# Main.net
KiCad netlist of a schematic drawn in Altium Designer
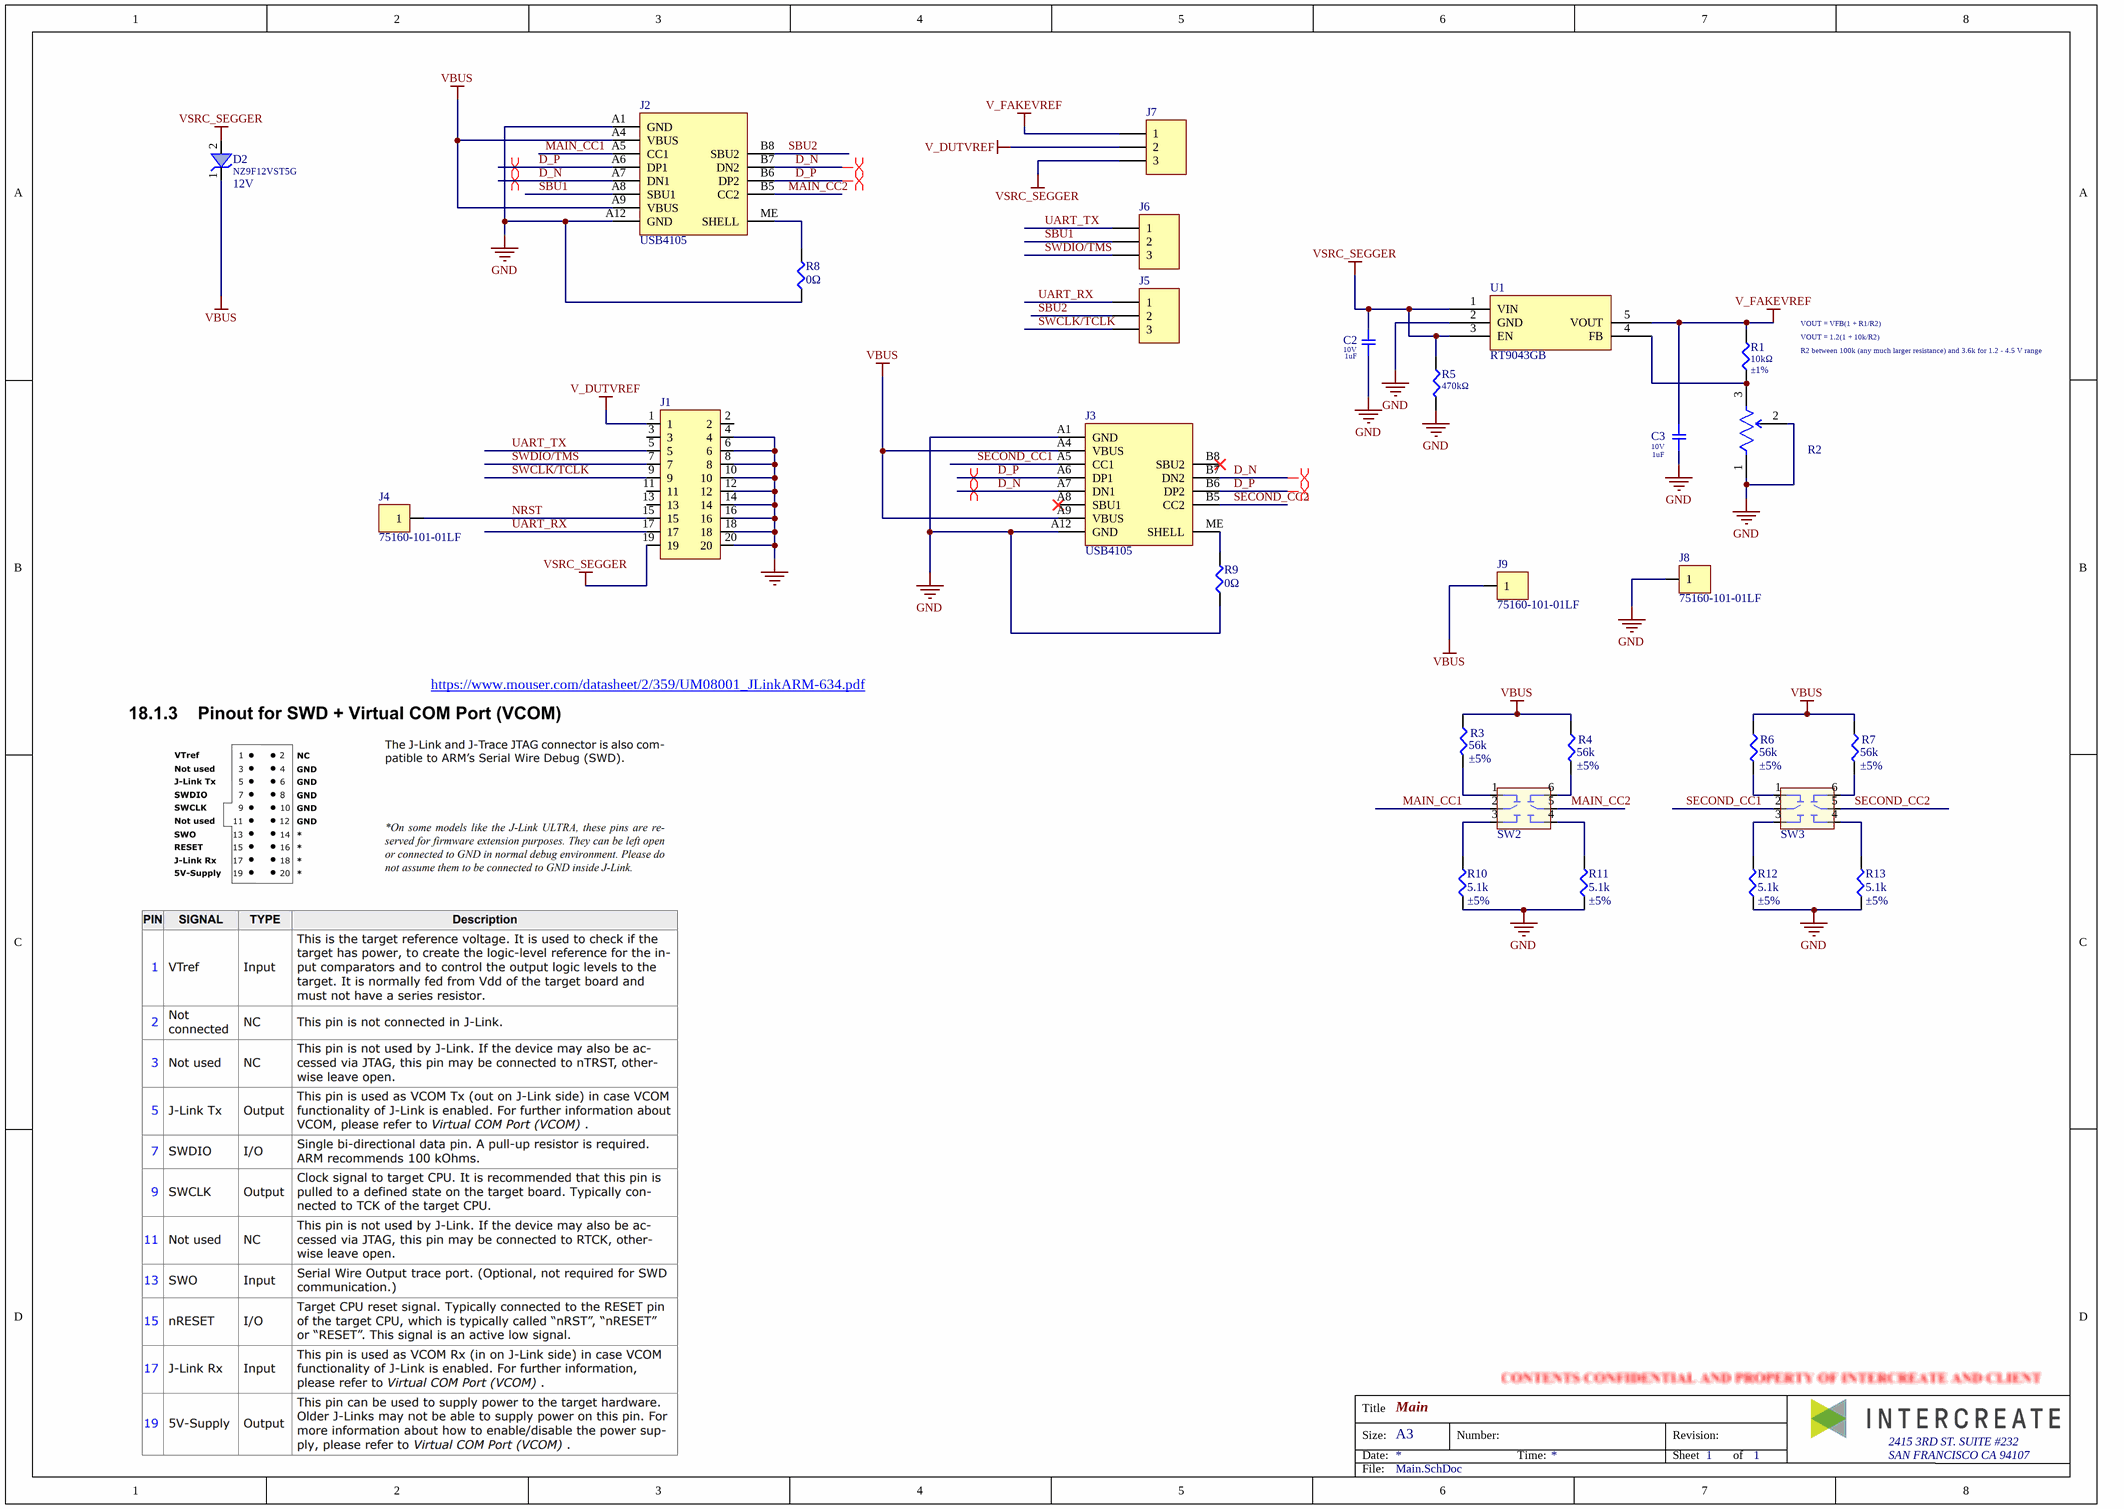
[diagram p0: Main.SchDoc]

(export (version "E")
  (design (tool "Eeschema 10.0.6"))
  (components
    (comp (ref "C2")
      (value "0402ZD105KAT2A")
      (footprint "CAP-0402")
      (fields
        (field (name "TOLERANCE") "10%")
        (field (name "VOLTAGE") "10V")
        (field (name "VOLTAGE RATING") "10V")
        (field (name "CAPACITANCE") "1uF")
      )
      (libsource (lib "intercreate") (part "CAP-1uF-10V-0402"))
    )
    (comp (ref "C3")
      (value "0402ZD105KAT2A")
      (footprint "CAP-0402")
      (fields
        (field (name "TOLERANCE") "10%")
        (field (name "VOLTAGE") "10V")
        (field (name "VOLTAGE RATING") "10V")
        (field (name "CAPACITANCE") "1uF")
      )
      (libsource (lib "intercreate") (part "CAP-1uF-10V-0402"))
    )
    (comp (ref "D2")
      (value "NZ9F12VST5G")
      (footprint "DIODE-SOD923")
      (description "DIODE ZENER 12V 200MW SOD923")
      (fields (field (name "TOLERANCE") "2%") (field (name "ZENER VOLTAGE") "12V"))
      (libsource (lib "intercreate") (part "DIODE-ZNR-12V-SOD923"))
    )
    (comp (ref "J1")
      (value "SFH11-PBPC-D10-ST-BK")
      (footprint "HDR-V-2X10-F-2.54MM")
      (description "20 Position Header Connector 0.100\" (2.54mm) Through Hole Gold")
      (libsource (lib "intercreate") (part "HDR-V-2X10-F-2.54MM"))
    )
    (comp (ref "J2")
      (value "USB4105")
      (footprint "CONN-USBC-GCT_USB4105")
      (description "Usb Conn, 2.0 Type C, Rcpt, 16Pos, Smt Rohs Compliant: Yes")
      (libsource (lib "intercreate") (part "CONN-F-USB-C-GCT_USB4105"))
    )
    (comp (ref "J3")
      (value "USB4105")
      (footprint "CONN-USBC-GCT_USB4105")
      (description "Usb Conn, 2.0 Type C, Rcpt, 16Pos, Smt Rohs Compliant: Yes")
      (libsource (lib "intercreate") (part "CONN-F-USB-C-GCT_USB4105"))
    )
    (comp (ref "J4")
      (value "75160-101-01LF")
      (footprint "HDR-V-1X1-M")
      (libsource (lib "") (part "HDR-V-1X1-M_1"))
    )
    (comp (ref "J5")
      (value "61300311121")
      (footprint "HDR-V-1X3")
      (description "Header, 3-Pin, 0.1\"")
      (fields (field (name "MANUFACTURER") "Wurth Electronics") (field (name "PUBLISHER") "Altium Limited"))
      (libsource (lib "intercreate") (part "HDR-V-1X3-M"))
    )
    (comp (ref "J6")
      (value "61300311121")
      (footprint "HDR-V-1X3")
      (description "Header, 3-Pin, 0.1\"")
      (fields (field (name "MANUFACTURER") "Wurth Electronics") (field (name "PUBLISHER") "Altium Limited"))
      (libsource (lib "intercreate") (part "HDR-V-1X3-M"))
    )
    (comp (ref "J7")
      (value "61300311121")
      (footprint "HDR-V-1X3")
      (description "Header, 3-Pin, 0.1\"")
      (fields (field (name "MANUFACTURER") "Wurth Electronics") (field (name "PUBLISHER") "Altium Limited"))
      (libsource (lib "intercreate") (part "HDR-V-1X3-M"))
    )
    (comp (ref "J8")
      (value "75160-101-01LF")
      (footprint "HDR-V-1X1-M")
      (libsource (lib "intercreate") (part "HDR-V-1X1-M"))
    )
    (comp (ref "J9")
      (value "75160-101-01LF")
      (footprint "HDR-V-1X1-M")
      (libsource (lib "intercreate") (part "HDR-V-1X1-M"))
    )
    (comp (ref "R1")
      (value "10kΩ")
      (footprint "RES-0402")
      (description "RES SMD 10K OHM 1% 1/16W 0402")
      (fields (field (name "TOLERANCE") "±1%") (field (name "Comment") "RC0402FR-0710KL"))
      (libsource (lib "intercreate") (part "RES-10K-0402"))
    )
    (comp (ref "R2")
      (value "POT-ROT-100K-SMD")
      (footprint "3361P-1-104GLF")
      (description "TRIMMER 100K OHM 0.5W GW TOP ADJ")
      (libsource (lib "intercreate") (part "POT-ROT-100K-SMD"))
    )
    (comp (ref "R3")
      (value "56k")
      (footprint "RES-0402")
      (description "RES SMD 56K OHM 5% 1/10W 0402")
      (fields
        (field (name "MANUFACTURER") "Panasonic")
        (field (name "MANUFACTURER PART NUMBER") "ERJ2GEJ563X")
        (field (name "TOLERANCE") "±5%")
      )
      (libsource (lib "intercreate") (part "RES-56K-0402-5%"))
    )
    (comp (ref "R4")
      (value "56k")
      (footprint "RES-0402")
      (description "RES SMD 56K OHM 5% 1/10W 0402")
      (fields
        (field (name "MANUFACTURER") "Panasonic")
        (field (name "MANUFACTURER PART NUMBER") "ERJ2GEJ563X")
        (field (name "TOLERANCE") "±5%")
      )
      (libsource (lib "intercreate") (part "RES-56K-0402-5%"))
    )
    (comp (ref "R5")
      (value "470kΩ")
      (footprint "RES-0402")
      (description "RES SMD 470K OHM 1% 1/16W 0402")
      (fields (field (name "TOLERANCE") "1%") (field (name "Comment") "RES-470K-0402"))
      (libsource (lib "Intercreate") (part "RES-95.3K-0402-0.1"))
    )
    (comp (ref "R6")
      (value "56k")
      (footprint "RES-0402")
      (description "RES SMD 56K OHM 5% 1/10W 0402")
      (fields
        (field (name "MANUFACTURER") "Panasonic")
        (field (name "MANUFACTURER PART NUMBER") "ERJ2GEJ563X")
        (field (name "TOLERANCE") "±5%")
      )
      (libsource (lib "intercreate") (part "RES-56K-0402-5%"))
    )
    (comp (ref "R7")
      (value "56k")
      (footprint "RES-0402")
      (description "RES SMD 56K OHM 5% 1/10W 0402")
      (fields
        (field (name "MANUFACTURER") "Panasonic")
        (field (name "MANUFACTURER PART NUMBER") "ERJ2GEJ563X")
        (field (name "TOLERANCE") "±5%")
      )
      (libsource (lib "intercreate") (part "RES-56K-0402-5%"))
    )
    (comp (ref "R8")
      (value "0Ω")
      (footprint "RES-0402")
      (description "RES 0 OHM JUMPER 1/16W 0402")
      (fields
        (field (name "MANUFACTURER") "Yageo")
        (field (name "MANUFACTURER PART NUMBER") "RC0402FR-070RL")
      )
      (libsource (lib "intercreate") (part "RES-0-0402"))
    )
    (comp (ref "R9")
      (value "0Ω")
      (footprint "RES-0402")
      (description "RES 0 OHM JUMPER 1/16W 0402")
      (fields
        (field (name "MANUFACTURER") "Yageo")
        (field (name "MANUFACTURER PART NUMBER") "RC0402FR-070RL")
      )
      (libsource (lib "intercreate") (part "RES-0-0402"))
    )
    (comp (ref "R10")
      (value "5.1k")
      (footprint "RES-0402")
      (description "RES SMD 5.1K OHM 5% 1/10W 0402")
      (fields (field (name "TOLERANCE") "±5%") (field (name "Comment") "ERJ2GEJ512X"))
      (libsource (lib "intercreate") (part "RES-5.1K-0402"))
    )
    (comp (ref "R11")
      (value "5.1k")
      (footprint "RES-0402")
      (description "RES SMD 5.1K OHM 5% 1/10W 0402")
      (fields (field (name "TOLERANCE") "±5%") (field (name "Comment") "ERJ2GEJ512X"))
      (libsource (lib "intercreate") (part "RES-5.1K-0402"))
    )
    (comp (ref "R12")
      (value "5.1k")
      (footprint "RES-0402")
      (description "RES SMD 5.1K OHM 5% 1/10W 0402")
      (fields (field (name "TOLERANCE") "±5%") (field (name "Comment") "ERJ2GEJ512X"))
      (libsource (lib "intercreate") (part "RES-5.1K-0402"))
    )
    (comp (ref "R13")
      (value "5.1k")
      (footprint "RES-0402")
      (description "RES SMD 5.1K OHM 5% 1/10W 0402")
      (fields (field (name "TOLERANCE") "±5%") (field (name "Comment") "ERJ2GEJ512X"))
      (libsource (lib "intercreate") (part "RES-5.1K-0402"))
    )
    (comp (ref "SW2")
      (value "CS-4-22YTA")
      (footprint "SW-BCD-CS-4-22YTA")
      (description "SWITCH ROTARY DIP DPDT 100MA 16V")
      (fields (field (name "MANUFACTURER") "Nidec Copal"))
      (libsource (lib "intercreate") (part "SW-DPDT-3P-ROTARY"))
    )
    (comp (ref "SW3")
      (value "CS-4-22YTA")
      (footprint "SW-BCD-CS-4-22YTA")
      (description "SWITCH ROTARY DIP DPDT 100MA 16V")
      (fields (field (name "MANUFACTURER") "Nidec Copal"))
      (libsource (lib "intercreate") (part "SW-DPDT-3P-ROTARY"))
    )
    (comp (ref "U1")
      (value "RT9043GB")
      (footprint "SOT-23-5")
      (description "IC REG LINEAR 3.3V 400mA SOT23-5")
      (libsource (lib "intercreate") (part "IC-PWR-LDO-RT9043GB"))
    )
  )
  (nets
    (net (code "1") (name "/D_N") (class "Default")
      (node (ref "J2") (pin "A7") (pinfunction "DN1_A7") (pintype "passive"))
      (node (ref "J2") (pin "B7") (pinfunction "DN2_B7") (pintype "passive"))
      (node (ref "J3") (pin "A7") (pinfunction "DN1_A7") (pintype "passive"))
      (node (ref "J3") (pin "B7") (pinfunction "DN2_B7") (pintype "passive"))
    )
    (net (code "2") (name "/D_P") (class "Default")
      (node (ref "J2") (pin "A6") (pinfunction "DP1_A6") (pintype "passive"))
      (node (ref "J2") (pin "B6") (pinfunction "DP2_B6") (pintype "passive"))
      (node (ref "J3") (pin "A6") (pinfunction "DP1_A6") (pintype "passive"))
      (node (ref "J3") (pin "B6") (pinfunction "DP2_B6") (pintype "passive"))
    )
    (net (code "3") (name "/MAIN_CC1") (class "Default")
      (node (ref "J2") (pin "A5") (pinfunction "CC1_A5") (pintype "passive"))
      (node (ref "SW2") (pin "2") (pinfunction "2_2") (pintype "passive"))
    )
    (net (code "4") (name "/MAIN_CC2") (class "Default")
      (node (ref "J2") (pin "B5") (pinfunction "CC2_B5") (pintype "passive"))
      (node (ref "SW2") (pin "5") (pinfunction "5_5") (pintype "passive"))
    )
    (net (code "5") (name "/NRST") (class "Default")
      (node (ref "J1") (pin "15") (pinfunction "15_15") (pintype "passive"))
      (node (ref "J4") (pin "1") (pinfunction "1_1") (pintype "passive"))
    )
    (net (code "6") (name "/SBU1") (class "Default")
      (node (ref "J2") (pin "A8") (pinfunction "SBU1_A8") (pintype "passive"))
      (node (ref "J6") (pin "2") (pinfunction "2_2") (pintype "passive"))
    )
    (net (code "7") (name "/SBU2") (class "Default")
      (node (ref "J2") (pin "B8") (pinfunction "SBU2_B8") (pintype "passive"))
      (node (ref "J5") (pin "2") (pinfunction "2_2") (pintype "passive"))
    )
    (net (code "8") (name "/SECOND_CC1") (class "Default")
      (node (ref "J3") (pin "A5") (pinfunction "CC1_A5") (pintype "passive"))
      (node (ref "SW3") (pin "2") (pinfunction "2_2") (pintype "passive"))
    )
    (net (code "9") (name "/SECOND_CC2") (class "Default")
      (node (ref "J3") (pin "B5") (pinfunction "CC2_B5") (pintype "passive"))
      (node (ref "SW3") (pin "5") (pinfunction "5_5") (pintype "passive"))
    )
    (net (code "10") (name "/SWCLK{slash}TCLK") (class "Default")
      (node (ref "J1") (pin "9") (pinfunction "9_9") (pintype "passive"))
      (node (ref "J5") (pin "3") (pinfunction "3_3") (pintype "passive"))
    )
    (net (code "11") (name "/SWDIO{slash}TMS") (class "Default")
      (node (ref "J1") (pin "7") (pinfunction "7_7") (pintype "passive"))
      (node (ref "J6") (pin "3") (pinfunction "3_3") (pintype "passive"))
    )
    (net (code "12") (name "/UART_RX") (class "Default")
      (node (ref "J1") (pin "17") (pinfunction "17_17") (pintype "passive"))
      (node (ref "J5") (pin "1") (pinfunction "1_1") (pintype "passive"))
    )
    (net (code "13") (name "/UART_TX") (class "Default")
      (node (ref "J1") (pin "5") (pinfunction "5_5") (pintype "passive"))
      (node (ref "J6") (pin "1") (pinfunction "1_1") (pintype "passive"))
    )
    (net (code "14") (name "GND") (class "Default")
      (node (ref "C2") (pin "1") (pinfunction "1_1") (pintype "passive"))
      (node (ref "C3") (pin "1") (pinfunction "1_1") (pintype "passive"))
      (node (ref "J1") (pin "10") (pinfunction "10_10") (pintype "passive"))
      (node (ref "J1") (pin "12") (pinfunction "12_12") (pintype "passive"))
      (node (ref "J1") (pin "14") (pinfunction "14_14") (pintype "passive"))
      (node (ref "J1") (pin "16") (pinfunction "16_16") (pintype "passive"))
      (node (ref "J1") (pin "18") (pinfunction "18_18") (pintype "passive"))
      (node (ref "J1") (pin "20") (pinfunction "20_20") (pintype "passive"))
      (node (ref "J1") (pin "4") (pinfunction "4_4") (pintype "passive"))
      (node (ref "J1") (pin "6") (pinfunction "6_6") (pintype "passive"))
      (node (ref "J1") (pin "8") (pinfunction "8_8") (pintype "passive"))
      (node (ref "J2") (pin "A1") (pinfunction "GND_A1") (pintype "passive"))
      (node (ref "J2") (pin "A12") (pinfunction "GND_A12") (pintype "passive"))
      (node (ref "J3") (pin "A1") (pinfunction "GND_A1") (pintype "passive"))
      (node (ref "J3") (pin "A12") (pinfunction "GND_A12") (pintype "passive"))
      (node (ref "J8") (pin "1") (pinfunction "1_1") (pintype "passive"))
      (node (ref "R10") (pin "1") (pinfunction "1_1") (pintype "passive"))
      (node (ref "R11") (pin "1") (pinfunction "1_1") (pintype "passive"))
      (node (ref "R12") (pin "1") (pinfunction "1_1") (pintype "passive"))
      (node (ref "R13") (pin "1") (pinfunction "1_1") (pintype "passive"))
      (node (ref "R2") (pin "1") (pinfunction "CCW_1") (pintype "passive"))
      (node (ref "R2") (pin "2") (pinfunction "WIPER_2") (pintype "passive"))
      (node (ref "R5") (pin "2") (pinfunction "2_2") (pintype "passive"))
      (node (ref "R8") (pin "1") (pinfunction "1_1") (pintype "passive"))
      (node (ref "R9") (pin "1") (pinfunction "1_1") (pintype "passive"))
      (node (ref "U1") (pin "2") (pinfunction "GND_2") (pintype "passive"))
    )
    (net (code "15") (name "Net-(J2-SHELL)") (class "Default")
      (node (ref "J2") (pin "ME") (pinfunction "SHELL_ME") (pintype "passive"))
      (node (ref "R8") (pin "2") (pinfunction "2_2") (pintype "passive"))
    )
    (net (code "16") (name "Net-(J3-SHELL)") (class "Default")
      (node (ref "J3") (pin "ME") (pinfunction "SHELL_ME") (pintype "passive"))
      (node (ref "R9") (pin "2") (pinfunction "2_2") (pintype "passive"))
    )
    (net (code "17") (name "Net-(R2-CW)") (class "Default")
      (node (ref "R1") (pin "1") (pinfunction "1_1") (pintype "passive"))
      (node (ref "R2") (pin "3") (pinfunction "CW_3") (pintype "passive"))
      (node (ref "U1") (pin "4") (pinfunction "FB_4") (pintype "passive"))
    )
    (net (code "18") (name "Net-(R3-Pad2)") (class "Default")
      (node (ref "R3") (pin "2") (pinfunction "2_2") (pintype "passive"))
      (node (ref "SW2") (pin "1") (pinfunction "1_1") (pintype "passive"))
    )
    (net (code "19") (name "Net-(R4-Pad2)") (class "Default")
      (node (ref "R4") (pin "2") (pinfunction "2_2") (pintype "passive"))
      (node (ref "SW2") (pin "6") (pinfunction "6_6") (pintype "passive"))
    )
    (net (code "20") (name "Net-(R6-Pad2)") (class "Default")
      (node (ref "R6") (pin "2") (pinfunction "2_2") (pintype "passive"))
      (node (ref "SW3") (pin "1") (pinfunction "1_1") (pintype "passive"))
    )
    (net (code "21") (name "Net-(R7-Pad2)") (class "Default")
      (node (ref "R7") (pin "2") (pinfunction "2_2") (pintype "passive"))
      (node (ref "SW3") (pin "6") (pinfunction "6_6") (pintype "passive"))
    )
    (net (code "22") (name "Net-(R10-Pad2)") (class "Default")
      (node (ref "R10") (pin "2") (pinfunction "2_2") (pintype "passive"))
      (node (ref "SW2") (pin "3") (pinfunction "3_3") (pintype "passive"))
    )
    (net (code "23") (name "Net-(R11-Pad2)") (class "Default")
      (node (ref "R11") (pin "2") (pinfunction "2_2") (pintype "passive"))
      (node (ref "SW2") (pin "4") (pinfunction "4_4") (pintype "passive"))
    )
    (net (code "24") (name "Net-(R12-Pad2)") (class "Default")
      (node (ref "R12") (pin "2") (pinfunction "2_2") (pintype "passive"))
      (node (ref "SW3") (pin "3") (pinfunction "3_3") (pintype "passive"))
    )
    (net (code "25") (name "Net-(R13-Pad2)") (class "Default")
      (node (ref "R13") (pin "2") (pinfunction "2_2") (pintype "passive"))
      (node (ref "SW3") (pin "4") (pinfunction "4_4") (pintype "passive"))
    )
    (net (code "26") (name "VBUS") (class "Default")
      (node (ref "D2") (pin "1") (pinfunction "K_1") (pintype "passive"))
      (node (ref "J2") (pin "A4") (pinfunction "VBUS_A4") (pintype "passive"))
      (node (ref "J2") (pin "A9") (pinfunction "VBUS_A9") (pintype "passive"))
      (node (ref "J3") (pin "A4") (pinfunction "VBUS_A4") (pintype "passive"))
      (node (ref "J3") (pin "A9") (pinfunction "VBUS_A9") (pintype "passive"))
      (node (ref "J9") (pin "1") (pinfunction "1_1") (pintype "passive"))
      (node (ref "R3") (pin "1") (pinfunction "1_1") (pintype "passive"))
      (node (ref "R4") (pin "1") (pinfunction "1_1") (pintype "passive"))
      (node (ref "R6") (pin "1") (pinfunction "1_1") (pintype "passive"))
      (node (ref "R7") (pin "1") (pinfunction "1_1") (pintype "passive"))
    )
    (net (code "27") (name "VSRC_SEGGER") (class "Default")
      (node (ref "C2") (pin "2") (pinfunction "2_2") (pintype "passive"))
      (node (ref "D2") (pin "2") (pinfunction "A_2") (pintype "passive"))
      (node (ref "J1") (pin "19") (pinfunction "19_19") (pintype "passive"))
      (node (ref "J7") (pin "3") (pinfunction "3_3") (pintype "passive"))
      (node (ref "R5") (pin "1") (pinfunction "1_1") (pintype "passive"))
      (node (ref "U1") (pin "1") (pinfunction "VIN_1") (pintype "passive"))
      (node (ref "U1") (pin "3") (pinfunction "EN_3") (pintype "passive"))
    )
    (net (code "28") (name "V_DUTVREF") (class "Default")
      (node (ref "J1") (pin "1") (pinfunction "1_1") (pintype "passive"))
      (node (ref "J7") (pin "2") (pinfunction "2_2") (pintype "passive"))
    )
    (net (code "29") (name "V_FAKEVREF") (class "Default")
      (node (ref "C3") (pin "2") (pinfunction "2_2") (pintype "passive"))
      (node (ref "J7") (pin "1") (pinfunction "1_1") (pintype "passive"))
      (node (ref "R1") (pin "2") (pinfunction "2_2") (pintype "passive"))
      (node (ref "U1") (pin "5") (pinfunction "VOUT_5") (pintype "passive"))
    )
    (net (code "30") (name "unconnected-(J1-Pad2)") (class "Default")
      (node (ref "J1") (pin "2") (pinfunction "2_2") (pintype "passive"))
    )
    (net (code "31") (name "unconnected-(J1-Pad3)") (class "Default")
      (node (ref "J1") (pin "3") (pinfunction "3_3") (pintype "passive"))
    )
    (net (code "32") (name "unconnected-(J1-Pad11)") (class "Default")
      (node (ref "J1") (pin "11") (pinfunction "11_11") (pintype "passive"))
    )
    (net (code "33") (name "unconnected-(J1-Pad13)") (class "Default")
      (node (ref "J1") (pin "13") (pinfunction "13_13") (pintype "passive"))
    )
    (net (code "34") (name "unconnected-(J3-SBU1-PadA8)") (class "Default")
      (node (ref "J3") (pin "A8") (pinfunction "SBU1_A8") (pintype "passive+no_connect"))
    )
    (net (code "35") (name "unconnected-(J3-SBU2-PadB8)") (class "Default")
      (node (ref "J3") (pin "B8") (pinfunction "SBU2_B8") (pintype "passive+no_connect"))
    )
  )
)
